# ProbeStationRelayBoard.net
KiCad netlist of a schematic drawn in EAGLE
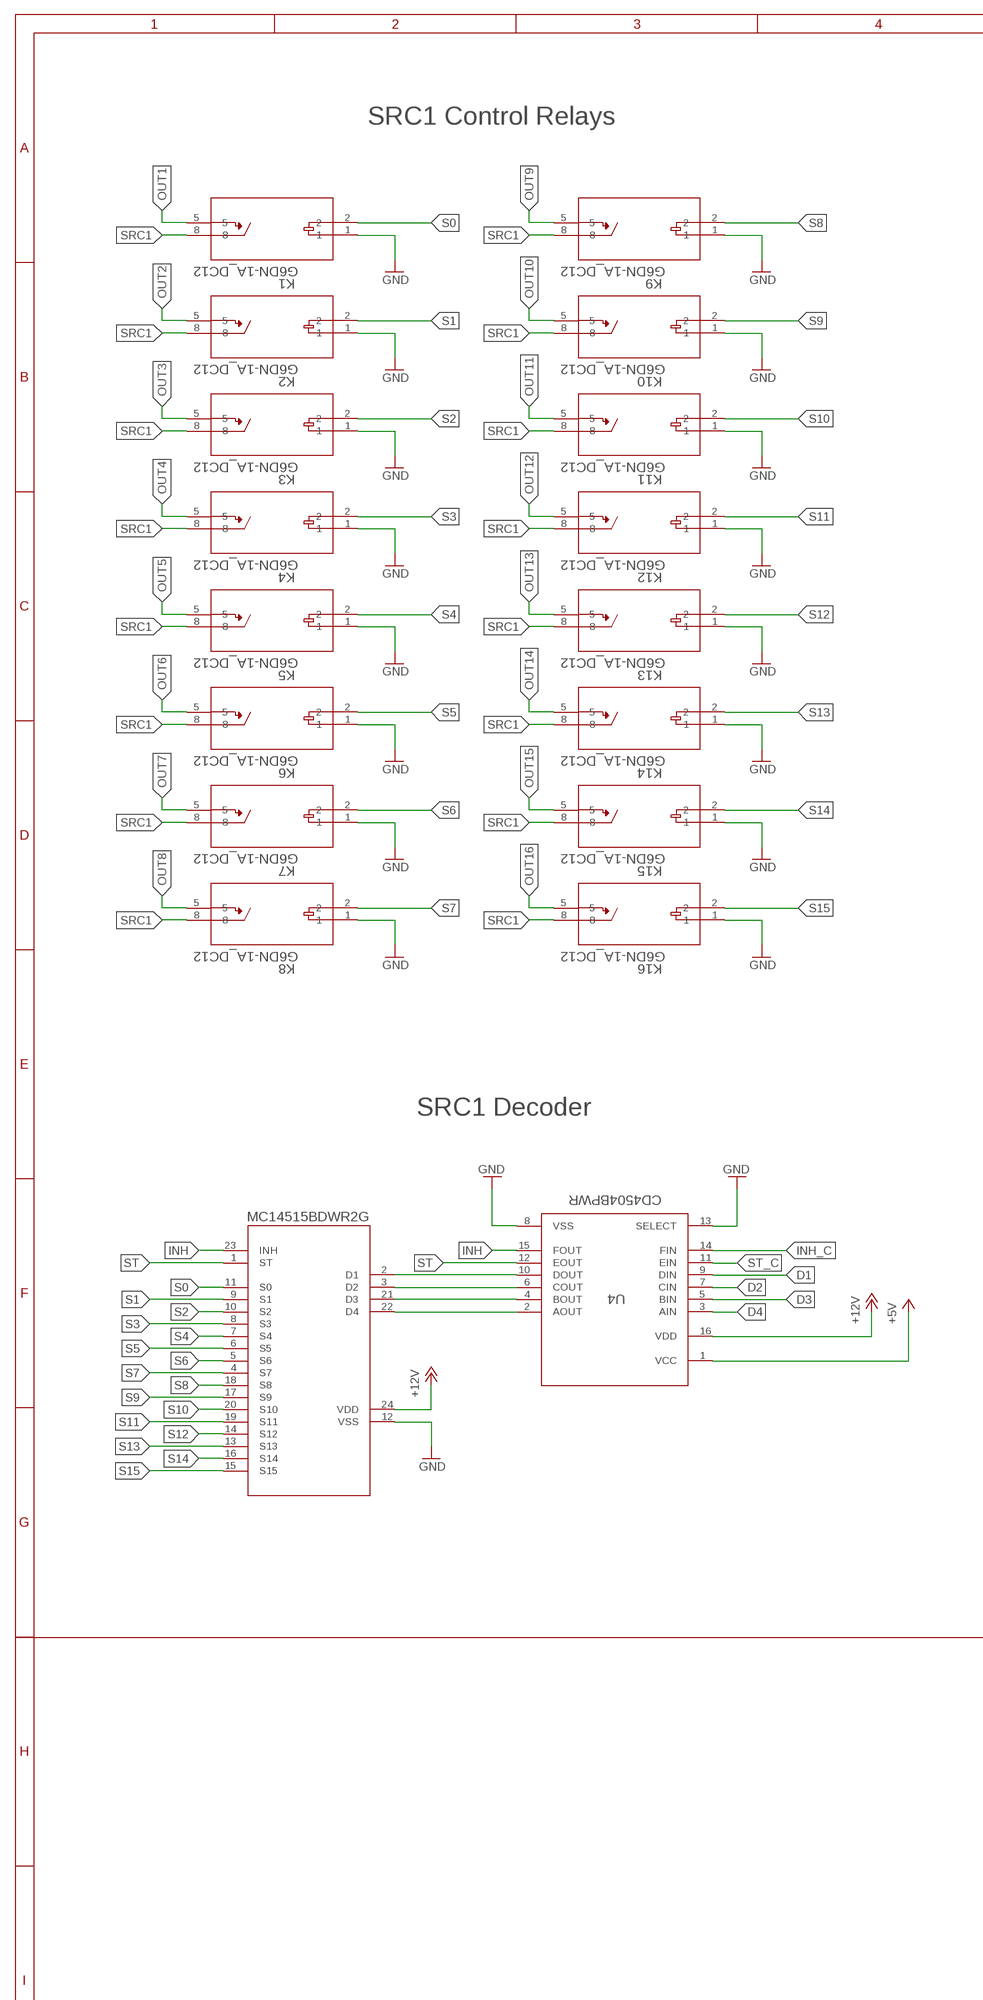
[diagram p0: schematic, sheet 1, part 1 of 2]
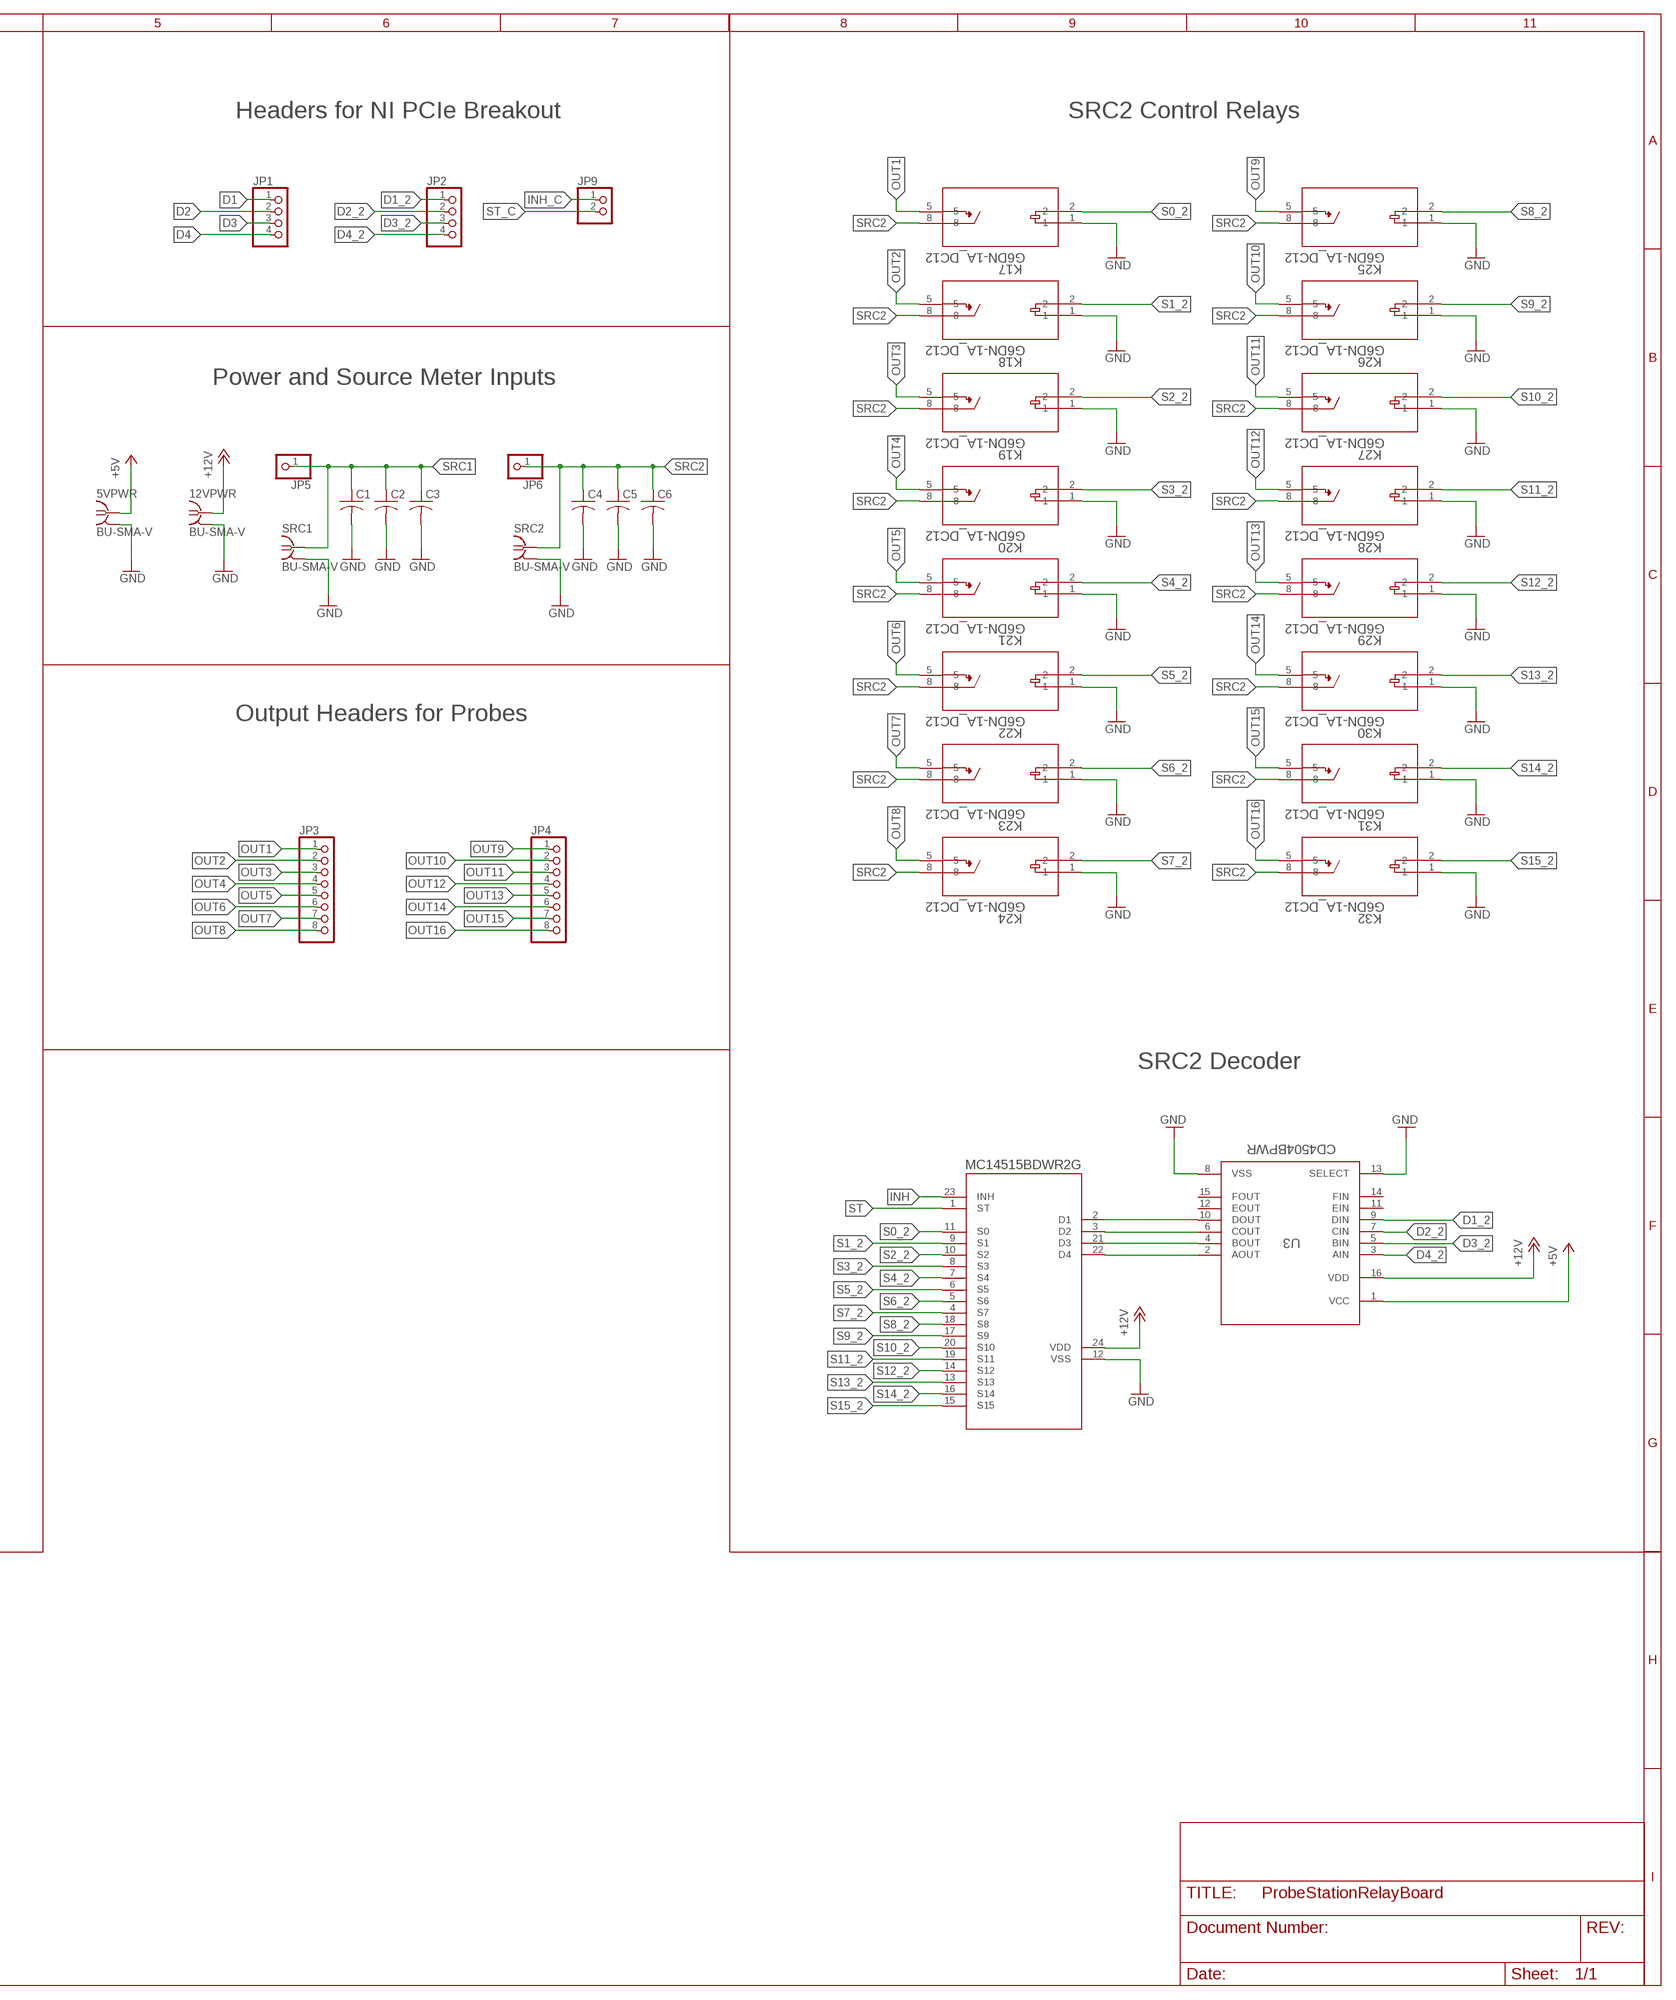
[diagram p1: schematic, sheet 1, part 2 of 2]

(export (version "E")
  (design (tool "Eeschema 10.0.6"))
  (components
    (comp (ref "5VPWR")
      (value "BU-SMA-V")
      (footprint "eagle-import:BU-SMA-V")
      (libsource (lib "eagle-import") (part "BU-SMA-V"))
    )
    (comp (ref "12VPWR")
      (value "BU-SMA-V")
      (footprint "eagle-import:BU-SMA-V")
      (libsource (lib "eagle-import") (part "BU-SMA-V"))
    )
    (comp (ref "C1")
      (value "C-USC0805")
      (footprint "eagle-import:C0805")
      (libsource (lib "eagle-import") (part "C-USC0805"))
    )
    (comp (ref "C2")
      (value "C-USC0805")
      (footprint "eagle-import:C0805")
      (libsource (lib "eagle-import") (part "C-USC0805"))
    )
    (comp (ref "C3")
      (value "C-USC0805")
      (footprint "eagle-import:C0805")
      (libsource (lib "eagle-import") (part "C-USC0805"))
    )
    (comp (ref "C4")
      (value "C-USC0805")
      (footprint "eagle-import:C0805")
      (libsource (lib "eagle-import") (part "C-USC0805"))
    )
    (comp (ref "C5")
      (value "C-USC0805")
      (footprint "eagle-import:C0805")
      (libsource (lib "eagle-import") (part "C-USC0805"))
    )
    (comp (ref "C6")
      (value "C-USC0805")
      (footprint "eagle-import:C0805")
      (libsource (lib "eagle-import") (part "C-USC0805"))
    )
    (comp (ref "JP1")
      (value "PINHD-1X4")
      (footprint "eagle-import:1X04")
      (libsource (lib "eagle-import") (part "PINHD-1X4"))
    )
    (comp (ref "JP2")
      (value "PINHD-1X4")
      (footprint "eagle-import:1X04")
      (libsource (lib "eagle-import") (part "PINHD-1X4"))
    )
    (comp (ref "JP3")
      (value "PINHD-1X8")
      (footprint "eagle-import:1X08")
      (libsource (lib "eagle-import") (part "PINHD-1X8"))
    )
    (comp (ref "JP4")
      (value "PINHD-1X8")
      (footprint "eagle-import:1X08")
      (libsource (lib "eagle-import") (part "PINHD-1X8"))
    )
    (comp (ref "JP5")
      (value "PINHD-1X1")
      (footprint "eagle-import:1X01")
      (libsource (lib "eagle-import") (part "PINHD-1X1"))
    )
    (comp (ref "JP6")
      (value "PINHD-1X1")
      (footprint "eagle-import:1X01")
      (libsource (lib "eagle-import") (part "PINHD-1X1"))
    )
    (comp (ref "JP9")
      (value "PINHD-1X2")
      (footprint "eagle-import:1X02")
      (libsource (lib "eagle-import") (part "PINHD-1X2"))
    )
    (comp (ref "K1")
      (value "G6DN-1A_DC12")
      (footprint "eagle-import:RELAY_G6DN-1A_OMR")
      (fields
        (field (name "MANUFACTURER_PART_NUMBER") "G6DN-1A DC12")
        (field (name "COPYRIGHT") "Copyright (C) 2021 Ultra Librarian. All rights reserved.")
      )
      (libsource (lib "eagle-import") (part "G6DN-1A_DC12"))
    )
    (comp (ref "K2")
      (value "G6DN-1A_DC12")
      (footprint "eagle-import:RELAY_G6DN-1A_OMR")
      (fields
        (field (name "MANUFACTURER_PART_NUMBER") "G6DN-1A DC12")
        (field (name "COPYRIGHT") "Copyright (C) 2021 Ultra Librarian. All rights reserved.")
      )
      (libsource (lib "eagle-import") (part "G6DN-1A_DC12"))
    )
    (comp (ref "K3")
      (value "G6DN-1A_DC12")
      (footprint "eagle-import:RELAY_G6DN-1A_OMR")
      (fields
        (field (name "MANUFACTURER_PART_NUMBER") "G6DN-1A DC12")
        (field (name "COPYRIGHT") "Copyright (C) 2021 Ultra Librarian. All rights reserved.")
      )
      (libsource (lib "eagle-import") (part "G6DN-1A_DC12"))
    )
    (comp (ref "K4")
      (value "G6DN-1A_DC12")
      (footprint "eagle-import:RELAY_G6DN-1A_OMR")
      (fields
        (field (name "MANUFACTURER_PART_NUMBER") "G6DN-1A DC12")
        (field (name "COPYRIGHT") "Copyright (C) 2021 Ultra Librarian. All rights reserved.")
      )
      (libsource (lib "eagle-import") (part "G6DN-1A_DC12"))
    )
    (comp (ref "K5")
      (value "G6DN-1A_DC12")
      (footprint "eagle-import:RELAY_G6DN-1A_OMR")
      (fields
        (field (name "MANUFACTURER_PART_NUMBER") "G6DN-1A DC12")
        (field (name "COPYRIGHT") "Copyright (C) 2021 Ultra Librarian. All rights reserved.")
      )
      (libsource (lib "eagle-import") (part "G6DN-1A_DC12"))
    )
    (comp (ref "K6")
      (value "G6DN-1A_DC12")
      (footprint "eagle-import:RELAY_G6DN-1A_OMR")
      (fields
        (field (name "MANUFACTURER_PART_NUMBER") "G6DN-1A DC12")
        (field (name "COPYRIGHT") "Copyright (C) 2021 Ultra Librarian. All rights reserved.")
      )
      (libsource (lib "eagle-import") (part "G6DN-1A_DC12"))
    )
    (comp (ref "K7")
      (value "G6DN-1A_DC12")
      (footprint "eagle-import:RELAY_G6DN-1A_OMR")
      (fields
        (field (name "MANUFACTURER_PART_NUMBER") "G6DN-1A DC12")
        (field (name "COPYRIGHT") "Copyright (C) 2021 Ultra Librarian. All rights reserved.")
      )
      (libsource (lib "eagle-import") (part "G6DN-1A_DC12"))
    )
    (comp (ref "K8")
      (value "G6DN-1A_DC12")
      (footprint "eagle-import:RELAY_G6DN-1A_OMR")
      (fields
        (field (name "MANUFACTURER_PART_NUMBER") "G6DN-1A DC12")
        (field (name "COPYRIGHT") "Copyright (C) 2021 Ultra Librarian. All rights reserved.")
      )
      (libsource (lib "eagle-import") (part "G6DN-1A_DC12"))
    )
    (comp (ref "K9")
      (value "G6DN-1A_DC12")
      (footprint "eagle-import:RELAY_G6DN-1A_OMR")
      (fields
        (field (name "MANUFACTURER_PART_NUMBER") "G6DN-1A DC12")
        (field (name "COPYRIGHT") "Copyright (C) 2021 Ultra Librarian. All rights reserved.")
      )
      (libsource (lib "eagle-import") (part "G6DN-1A_DC12"))
    )
    (comp (ref "K10")
      (value "G6DN-1A_DC12")
      (footprint "eagle-import:RELAY_G6DN-1A_OMR")
      (fields
        (field (name "MANUFACTURER_PART_NUMBER") "G6DN-1A DC12")
        (field (name "COPYRIGHT") "Copyright (C) 2021 Ultra Librarian. All rights reserved.")
      )
      (libsource (lib "eagle-import") (part "G6DN-1A_DC12"))
    )
    (comp (ref "K11")
      (value "G6DN-1A_DC12")
      (footprint "eagle-import:RELAY_G6DN-1A_OMR")
      (fields
        (field (name "MANUFACTURER_PART_NUMBER") "G6DN-1A DC12")
        (field (name "COPYRIGHT") "Copyright (C) 2021 Ultra Librarian. All rights reserved.")
      )
      (libsource (lib "eagle-import") (part "G6DN-1A_DC12"))
    )
    (comp (ref "K12")
      (value "G6DN-1A_DC12")
      (footprint "eagle-import:RELAY_G6DN-1A_OMR")
      (fields
        (field (name "MANUFACTURER_PART_NUMBER") "G6DN-1A DC12")
        (field (name "COPYRIGHT") "Copyright (C) 2021 Ultra Librarian. All rights reserved.")
      )
      (libsource (lib "eagle-import") (part "G6DN-1A_DC12"))
    )
    (comp (ref "K13")
      (value "G6DN-1A_DC12")
      (footprint "eagle-import:RELAY_G6DN-1A_OMR")
      (fields
        (field (name "MANUFACTURER_PART_NUMBER") "G6DN-1A DC12")
        (field (name "COPYRIGHT") "Copyright (C) 2021 Ultra Librarian. All rights reserved.")
      )
      (libsource (lib "eagle-import") (part "G6DN-1A_DC12"))
    )
    (comp (ref "K14")
      (value "G6DN-1A_DC12")
      (footprint "eagle-import:RELAY_G6DN-1A_OMR")
      (fields
        (field (name "MANUFACTURER_PART_NUMBER") "G6DN-1A DC12")
        (field (name "COPYRIGHT") "Copyright (C) 2021 Ultra Librarian. All rights reserved.")
      )
      (libsource (lib "eagle-import") (part "G6DN-1A_DC12"))
    )
    (comp (ref "K15")
      (value "G6DN-1A_DC12")
      (footprint "eagle-import:RELAY_G6DN-1A_OMR")
      (fields
        (field (name "MANUFACTURER_PART_NUMBER") "G6DN-1A DC12")
        (field (name "COPYRIGHT") "Copyright (C) 2021 Ultra Librarian. All rights reserved.")
      )
      (libsource (lib "eagle-import") (part "G6DN-1A_DC12"))
    )
    (comp (ref "K16")
      (value "G6DN-1A_DC12")
      (footprint "eagle-import:RELAY_G6DN-1A_OMR")
      (fields
        (field (name "MANUFACTURER_PART_NUMBER") "G6DN-1A DC12")
        (field (name "COPYRIGHT") "Copyright (C) 2021 Ultra Librarian. All rights reserved.")
      )
      (libsource (lib "eagle-import") (part "G6DN-1A_DC12"))
    )
    (comp (ref "K17")
      (value "G6DN-1A_DC12")
      (footprint "eagle-import:RELAY_G6DN-1A_OMR")
      (fields
        (field (name "MANUFACTURER_PART_NUMBER") "G6DN-1A DC12")
        (field (name "COPYRIGHT") "Copyright (C) 2021 Ultra Librarian. All rights reserved.")
      )
      (libsource (lib "eagle-import") (part "G6DN-1A_DC12"))
    )
    (comp (ref "K18")
      (value "G6DN-1A_DC12")
      (footprint "eagle-import:RELAY_G6DN-1A_OMR")
      (fields
        (field (name "MANUFACTURER_PART_NUMBER") "G6DN-1A DC12")
        (field (name "COPYRIGHT") "Copyright (C) 2021 Ultra Librarian. All rights reserved.")
      )
      (libsource (lib "eagle-import") (part "G6DN-1A_DC12"))
    )
    (comp (ref "K19")
      (value "G6DN-1A_DC12")
      (footprint "eagle-import:RELAY_G6DN-1A_OMR")
      (fields
        (field (name "MANUFACTURER_PART_NUMBER") "G6DN-1A DC12")
        (field (name "COPYRIGHT") "Copyright (C) 2021 Ultra Librarian. All rights reserved.")
      )
      (libsource (lib "eagle-import") (part "G6DN-1A_DC12"))
    )
    (comp (ref "K20")
      (value "G6DN-1A_DC12")
      (footprint "eagle-import:RELAY_G6DN-1A_OMR")
      (fields
        (field (name "MANUFACTURER_PART_NUMBER") "G6DN-1A DC12")
        (field (name "COPYRIGHT") "Copyright (C) 2021 Ultra Librarian. All rights reserved.")
      )
      (libsource (lib "eagle-import") (part "G6DN-1A_DC12"))
    )
    (comp (ref "K21")
      (value "G6DN-1A_DC12")
      (footprint "eagle-import:RELAY_G6DN-1A_OMR")
      (fields
        (field (name "MANUFACTURER_PART_NUMBER") "G6DN-1A DC12")
        (field (name "COPYRIGHT") "Copyright (C) 2021 Ultra Librarian. All rights reserved.")
      )
      (libsource (lib "eagle-import") (part "G6DN-1A_DC12"))
    )
    (comp (ref "K22")
      (value "G6DN-1A_DC12")
      (footprint "eagle-import:RELAY_G6DN-1A_OMR")
      (fields
        (field (name "MANUFACTURER_PART_NUMBER") "G6DN-1A DC12")
        (field (name "COPYRIGHT") "Copyright (C) 2021 Ultra Librarian. All rights reserved.")
      )
      (libsource (lib "eagle-import") (part "G6DN-1A_DC12"))
    )
    (comp (ref "K23")
      (value "G6DN-1A_DC12")
      (footprint "eagle-import:RELAY_G6DN-1A_OMR")
      (fields
        (field (name "MANUFACTURER_PART_NUMBER") "G6DN-1A DC12")
        (field (name "COPYRIGHT") "Copyright (C) 2021 Ultra Librarian. All rights reserved.")
      )
      (libsource (lib "eagle-import") (part "G6DN-1A_DC12"))
    )
    (comp (ref "K24")
      (value "G6DN-1A_DC12")
      (footprint "eagle-import:RELAY_G6DN-1A_OMR")
      (fields
        (field (name "MANUFACTURER_PART_NUMBER") "G6DN-1A DC12")
        (field (name "COPYRIGHT") "Copyright (C) 2021 Ultra Librarian. All rights reserved.")
      )
      (libsource (lib "eagle-import") (part "G6DN-1A_DC12"))
    )
    (comp (ref "K25")
      (value "G6DN-1A_DC12")
      (footprint "eagle-import:RELAY_G6DN-1A_OMR")
      (fields
        (field (name "MANUFACTURER_PART_NUMBER") "G6DN-1A DC12")
        (field (name "COPYRIGHT") "Copyright (C) 2021 Ultra Librarian. All rights reserved.")
      )
      (libsource (lib "eagle-import") (part "G6DN-1A_DC12"))
    )
    (comp (ref "K26")
      (value "G6DN-1A_DC12")
      (footprint "eagle-import:RELAY_G6DN-1A_OMR")
      (fields
        (field (name "MANUFACTURER_PART_NUMBER") "G6DN-1A DC12")
        (field (name "COPYRIGHT") "Copyright (C) 2021 Ultra Librarian. All rights reserved.")
      )
      (libsource (lib "eagle-import") (part "G6DN-1A_DC12"))
    )
    (comp (ref "K27")
      (value "G6DN-1A_DC12")
      (footprint "eagle-import:RELAY_G6DN-1A_OMR")
      (fields
        (field (name "MANUFACTURER_PART_NUMBER") "G6DN-1A DC12")
        (field (name "COPYRIGHT") "Copyright (C) 2021 Ultra Librarian. All rights reserved.")
      )
      (libsource (lib "eagle-import") (part "G6DN-1A_DC12"))
    )
    (comp (ref "K28")
      (value "G6DN-1A_DC12")
      (footprint "eagle-import:RELAY_G6DN-1A_OMR")
      (fields
        (field (name "MANUFACTURER_PART_NUMBER") "G6DN-1A DC12")
        (field (name "COPYRIGHT") "Copyright (C) 2021 Ultra Librarian. All rights reserved.")
      )
      (libsource (lib "eagle-import") (part "G6DN-1A_DC12"))
    )
    (comp (ref "K29")
      (value "G6DN-1A_DC12")
      (footprint "eagle-import:RELAY_G6DN-1A_OMR")
      (fields
        (field (name "MANUFACTURER_PART_NUMBER") "G6DN-1A DC12")
        (field (name "COPYRIGHT") "Copyright (C) 2021 Ultra Librarian. All rights reserved.")
      )
      (libsource (lib "eagle-import") (part "G6DN-1A_DC12"))
    )
    (comp (ref "K30")
      (value "G6DN-1A_DC12")
      (footprint "eagle-import:RELAY_G6DN-1A_OMR")
      (fields
        (field (name "MANUFACTURER_PART_NUMBER") "G6DN-1A DC12")
        (field (name "COPYRIGHT") "Copyright (C) 2021 Ultra Librarian. All rights reserved.")
      )
      (libsource (lib "eagle-import") (part "G6DN-1A_DC12"))
    )
    (comp (ref "K31")
      (value "G6DN-1A_DC12")
      (footprint "eagle-import:RELAY_G6DN-1A_OMR")
      (fields
        (field (name "MANUFACTURER_PART_NUMBER") "G6DN-1A DC12")
        (field (name "COPYRIGHT") "Copyright (C) 2021 Ultra Librarian. All rights reserved.")
      )
      (libsource (lib "eagle-import") (part "G6DN-1A_DC12"))
    )
    (comp (ref "K32")
      (value "G6DN-1A_DC12")
      (footprint "eagle-import:RELAY_G6DN-1A_OMR")
      (fields
        (field (name "MANUFACTURER_PART_NUMBER") "G6DN-1A DC12")
        (field (name "COPYRIGHT") "Copyright (C) 2021 Ultra Librarian. All rights reserved.")
      )
      (libsource (lib "eagle-import") (part "G6DN-1A_DC12"))
    )
    (comp (ref "SRC1")
      (value "BU-SMA-V")
      (footprint "eagle-import:BU-SMA-V")
      (libsource (lib "eagle-import") (part "BU-SMA-V"))
    )
    (comp (ref "SRC2")
      (value "BU-SMA-V")
      (footprint "eagle-import:BU-SMA-V")
      (libsource (lib "eagle-import") (part "BU-SMA-V"))
    )
    (comp (ref "U1")
      (value "MC14515BDWR2G")
      (footprint "eagle-import:SOIC-24WB_ONS")
      (fields (field (name "COPYRIGHT") "Copyright (C) 2021 Ultra Librarian. All rights reserved."))
      (libsource (lib "eagle-import") (part "MC14515BDWR2G"))
    )
    (comp (ref "U2")
      (value "MC14515BDWR2G")
      (footprint "eagle-import:SOIC-24WB_ONS")
      (fields (field (name "COPYRIGHT") "Copyright (C) 2021 Ultra Librarian. All rights reserved."))
      (libsource (lib "eagle-import") (part "MC14515BDWR2G"))
    )
    (comp (ref "U3")
      (value "CD4504BPWR")
      (footprint "eagle-import:PW0016A_N")
      (fields (field (name "COPYRIGHT") "Copyright (C) 2021 Ultra Librarian. All rights reserved."))
      (libsource (lib "eagle-import") (part "CD4504BPWR"))
    )
    (comp (ref "U4")
      (value "CD4504BPWR")
      (footprint "eagle-import:PW0016A_N")
      (fields (field (name "COPYRIGHT") "Copyright (C) 2021 Ultra Librarian. All rights reserved."))
      (libsource (lib "eagle-import") (part "CD4504BPWR"))
    )
  )
  (nets
    (net (code "1") (name "+5V") (class "Default")
      (node (ref "5VPWR") (pin "1") (pinfunction "1_1") (pintype "passive"))
      (node (ref "U3") (pin "1") (pinfunction "VCC_1") (pintype "power_in"))
      (node (ref "U4") (pin "1") (pinfunction "VCC_1") (pintype "power_in"))
    )
    (net (code "2") (name "+12V") (class "Default")
      (node (ref "12VPWR") (pin "1") (pinfunction "1_1") (pintype "passive"))
      (node (ref "U1") (pin "24") (pinfunction "VDD_24") (pintype "power_in"))
      (node (ref "U2") (pin "24") (pinfunction "VDD_24") (pintype "power_in"))
      (node (ref "U3") (pin "16") (pinfunction "VDD_16") (pintype "power_in"))
      (node (ref "U4") (pin "16") (pinfunction "VDD_16") (pintype "power_in"))
    )
    (net (code "3") (name "D1") (class "Default")
      (node (ref "JP1") (pin "1") (pinfunction "1_1") (pintype "passive"))
      (node (ref "U4") (pin "9") (pinfunction "DIN_9") (pintype "input"))
    )
    (net (code "4") (name "D1_2") (class "Default")
      (node (ref "JP2") (pin "1") (pinfunction "1_1") (pintype "passive"))
      (node (ref "U3") (pin "9") (pinfunction "DIN_9") (pintype "input"))
    )
    (net (code "5") (name "D2") (class "Default")
      (node (ref "JP1") (pin "2") (pinfunction "2_2") (pintype "passive"))
      (node (ref "U4") (pin "7") (pinfunction "CIN_7") (pintype "input"))
    )
    (net (code "6") (name "D2_2") (class "Default")
      (node (ref "JP2") (pin "2") (pinfunction "2_2") (pintype "passive"))
      (node (ref "U3") (pin "7") (pinfunction "CIN_7") (pintype "input"))
    )
    (net (code "7") (name "D3") (class "Default")
      (node (ref "JP1") (pin "3") (pinfunction "3_3") (pintype "passive"))
      (node (ref "U4") (pin "5") (pinfunction "BIN_5") (pintype "input"))
    )
    (net (code "8") (name "D3_2") (class "Default")
      (node (ref "JP2") (pin "3") (pinfunction "3_3") (pintype "passive"))
      (node (ref "U3") (pin "5") (pinfunction "BIN_5") (pintype "input"))
    )
    (net (code "9") (name "D4") (class "Default")
      (node (ref "JP1") (pin "4") (pinfunction "4_4") (pintype "passive"))
      (node (ref "U4") (pin "3") (pinfunction "AIN_3") (pintype "input"))
    )
    (net (code "10") (name "D4_2") (class "Default")
      (node (ref "JP2") (pin "4") (pinfunction "4_4") (pintype "passive"))
      (node (ref "U3") (pin "3") (pinfunction "AIN_3") (pintype "input"))
    )
    (net (code "11") (name "GND") (class "Default")
      (node (ref "12VPWR") (pin "2") (pinfunction "2_2") (pintype "passive"))
      (node (ref "12VPWR") (pin "3") (pinfunction "2_3") (pintype "passive"))
      (node (ref "12VPWR") (pin "4") (pinfunction "2_4") (pintype "passive"))
      (node (ref "12VPWR") (pin "5") (pinfunction "2_5") (pintype "passive"))
      (node (ref "5VPWR") (pin "2") (pinfunction "2_2") (pintype "passive"))
      (node (ref "5VPWR") (pin "3") (pinfunction "2_3") (pintype "passive"))
      (node (ref "5VPWR") (pin "4") (pinfunction "2_4") (pintype "passive"))
      (node (ref "5VPWR") (pin "5") (pinfunction "2_5") (pintype "passive"))
      (node (ref "C1") (pin "2") (pinfunction "2_2") (pintype "passive"))
      (node (ref "C2") (pin "2") (pinfunction "2_2") (pintype "passive"))
      (node (ref "C3") (pin "2") (pinfunction "2_2") (pintype "passive"))
      (node (ref "C4") (pin "2") (pinfunction "2_2") (pintype "passive"))
      (node (ref "C5") (pin "2") (pinfunction "2_2") (pintype "passive"))
      (node (ref "C6") (pin "2") (pinfunction "2_2") (pintype "passive"))
      (node (ref "K1") (pin "1") (pinfunction "1_1") (pintype "passive"))
      (node (ref "K10") (pin "1") (pinfunction "1_1") (pintype "passive"))
      (node (ref "K11") (pin "1") (pinfunction "1_1") (pintype "passive"))
      (node (ref "K12") (pin "1") (pinfunction "1_1") (pintype "passive"))
      (node (ref "K13") (pin "1") (pinfunction "1_1") (pintype "passive"))
      (node (ref "K14") (pin "1") (pinfunction "1_1") (pintype "passive"))
      (node (ref "K15") (pin "1") (pinfunction "1_1") (pintype "passive"))
      (node (ref "K16") (pin "1") (pinfunction "1_1") (pintype "passive"))
      (node (ref "K17") (pin "1") (pinfunction "1_1") (pintype "passive"))
      (node (ref "K18") (pin "1") (pinfunction "1_1") (pintype "passive"))
      (node (ref "K19") (pin "1") (pinfunction "1_1") (pintype "passive"))
      (node (ref "K2") (pin "1") (pinfunction "1_1") (pintype "passive"))
      (node (ref "K20") (pin "1") (pinfunction "1_1") (pintype "passive"))
      (node (ref "K21") (pin "1") (pinfunction "1_1") (pintype "passive"))
      (node (ref "K22") (pin "1") (pinfunction "1_1") (pintype "passive"))
      (node (ref "K23") (pin "1") (pinfunction "1_1") (pintype "passive"))
      (node (ref "K24") (pin "1") (pinfunction "1_1") (pintype "passive"))
      (node (ref "K25") (pin "1") (pinfunction "1_1") (pintype "passive"))
      (node (ref "K26") (pin "1") (pinfunction "1_1") (pintype "passive"))
      (node (ref "K27") (pin "1") (pinfunction "1_1") (pintype "passive"))
      (node (ref "K28") (pin "1") (pinfunction "1_1") (pintype "passive"))
      (node (ref "K29") (pin "1") (pinfunction "1_1") (pintype "passive"))
      (node (ref "K3") (pin "1") (pinfunction "1_1") (pintype "passive"))
      (node (ref "K30") (pin "1") (pinfunction "1_1") (pintype "passive"))
      (node (ref "K31") (pin "1") (pinfunction "1_1") (pintype "passive"))
      (node (ref "K32") (pin "1") (pinfunction "1_1") (pintype "passive"))
      (node (ref "K4") (pin "1") (pinfunction "1_1") (pintype "passive"))
      (node (ref "K5") (pin "1") (pinfunction "1_1") (pintype "passive"))
      (node (ref "K6") (pin "1") (pinfunction "1_1") (pintype "passive"))
      (node (ref "K7") (pin "1") (pinfunction "1_1") (pintype "passive"))
      (node (ref "K8") (pin "1") (pinfunction "1_1") (pintype "passive"))
      (node (ref "K9") (pin "1") (pinfunction "1_1") (pintype "passive"))
      (node (ref "SRC1") (pin "2") (pinfunction "2_2") (pintype "passive"))
      (node (ref "SRC1") (pin "3") (pinfunction "2_3") (pintype "passive"))
      (node (ref "SRC1") (pin "4") (pinfunction "2_4") (pintype "passive"))
      (node (ref "SRC1") (pin "5") (pinfunction "2_5") (pintype "passive"))
      (node (ref "SRC2") (pin "2") (pinfunction "2_2") (pintype "passive"))
      (node (ref "SRC2") (pin "3") (pinfunction "2_3") (pintype "passive"))
      (node (ref "SRC2") (pin "4") (pinfunction "2_4") (pintype "passive"))
      (node (ref "SRC2") (pin "5") (pinfunction "2_5") (pintype "passive"))
      (node (ref "U1") (pin "12") (pinfunction "VSS_12") (pintype "power_in"))
      (node (ref "U2") (pin "12") (pinfunction "VSS_12") (pintype "power_in"))
      (node (ref "U3") (pin "13") (pinfunction "SELECT_13") (pintype "input"))
      (node (ref "U3") (pin "8") (pinfunction "VSS_8") (pintype "power_in"))
      (node (ref "U4") (pin "13") (pinfunction "SELECT_13") (pintype "input"))
      (node (ref "U4") (pin "8") (pinfunction "VSS_8") (pintype "power_in"))
    )
    (net (code "12") (name "INH") (class "Default")
      (node (ref "U1") (pin "23") (pinfunction "INH_23") (pintype "passive"))
      (node (ref "U2") (pin "23") (pinfunction "INH_23") (pintype "passive"))
      (node (ref "U4") (pin "15") (pinfunction "FOUT_15") (pintype "output"))
    )
    (net (code "13") (name "INH_C") (class "Default")
      (node (ref "JP9") (pin "1") (pinfunction "1_1") (pintype "passive"))
      (node (ref "U4") (pin "14") (pinfunction "FIN_14") (pintype "input"))
    )
    (net (code "14") (name "Net-(U1-D1)") (class "Default")
      (node (ref "U1") (pin "2") (pinfunction "D1_2") (pintype "passive"))
      (node (ref "U3") (pin "10") (pinfunction "DOUT_10") (pintype "output"))
    )
    (net (code "15") (name "Net-(U1-D2)") (class "Default")
      (node (ref "U1") (pin "3") (pinfunction "D2_3") (pintype "passive"))
      (node (ref "U3") (pin "6") (pinfunction "COUT_6") (pintype "output"))
    )
    (net (code "16") (name "Net-(U1-D3)") (class "Default")
      (node (ref "U1") (pin "21") (pinfunction "D3_21") (pintype "passive"))
      (node (ref "U3") (pin "4") (pinfunction "BOUT_4") (pintype "output"))
    )
    (net (code "17") (name "Net-(U1-D4)") (class "Default")
      (node (ref "U1") (pin "22") (pinfunction "D4_22") (pintype "passive"))
      (node (ref "U3") (pin "2") (pinfunction "AOUT_2") (pintype "output"))
    )
    (net (code "18") (name "Net-(U2-D1)") (class "Default")
      (node (ref "U2") (pin "2") (pinfunction "D1_2") (pintype "passive"))
      (node (ref "U4") (pin "10") (pinfunction "DOUT_10") (pintype "output"))
    )
    (net (code "19") (name "Net-(U2-D2)") (class "Default")
      (node (ref "U2") (pin "3") (pinfunction "D2_3") (pintype "passive"))
      (node (ref "U4") (pin "6") (pinfunction "COUT_6") (pintype "output"))
    )
    (net (code "20") (name "Net-(U2-D3)") (class "Default")
      (node (ref "U2") (pin "21") (pinfunction "D3_21") (pintype "passive"))
      (node (ref "U4") (pin "4") (pinfunction "BOUT_4") (pintype "output"))
    )
    (net (code "21") (name "Net-(U2-D4)") (class "Default")
      (node (ref "U2") (pin "22") (pinfunction "D4_22") (pintype "passive"))
      (node (ref "U4") (pin "2") (pinfunction "AOUT_2") (pintype "output"))
    )
    (net (code "22") (name "OUT1") (class "Default")
      (node (ref "JP3") (pin "1") (pinfunction "1_1") (pintype "passive"))
      (node (ref "K1") (pin "5") (pinfunction "5_5") (pintype "passive"))
      (node (ref "K17") (pin "5") (pinfunction "5_5") (pintype "passive"))
    )
    (net (code "23") (name "OUT2") (class "Default")
      (node (ref "JP3") (pin "2") (pinfunction "2_2") (pintype "passive"))
      (node (ref "K18") (pin "5") (pinfunction "5_5") (pintype "passive"))
      (node (ref "K2") (pin "5") (pinfunction "5_5") (pintype "passive"))
    )
    (net (code "24") (name "OUT3") (class "Default")
      (node (ref "JP3") (pin "3") (pinfunction "3_3") (pintype "passive"))
      (node (ref "K19") (pin "5") (pinfunction "5_5") (pintype "passive"))
      (node (ref "K3") (pin "5") (pinfunction "5_5") (pintype "passive"))
    )
    (net (code "25") (name "OUT4") (class "Default")
      (node (ref "JP3") (pin "4") (pinfunction "4_4") (pintype "passive"))
      (node (ref "K20") (pin "5") (pinfunction "5_5") (pintype "passive"))
      (node (ref "K4") (pin "5") (pinfunction "5_5") (pintype "passive"))
    )
    (net (code "26") (name "OUT5") (class "Default")
      (node (ref "JP3") (pin "5") (pinfunction "5_5") (pintype "passive"))
      (node (ref "K21") (pin "5") (pinfunction "5_5") (pintype "passive"))
      (node (ref "K5") (pin "5") (pinfunction "5_5") (pintype "passive"))
    )
    (net (code "27") (name "OUT6") (class "Default")
      (node (ref "JP3") (pin "6") (pinfunction "6_6") (pintype "passive"))
      (node (ref "K22") (pin "5") (pinfunction "5_5") (pintype "passive"))
      (node (ref "K6") (pin "5") (pinfunction "5_5") (pintype "passive"))
    )
    (net (code "28") (name "OUT7") (class "Default")
      (node (ref "JP3") (pin "7") (pinfunction "7_7") (pintype "passive"))
      (node (ref "K23") (pin "5") (pinfunction "5_5") (pintype "passive"))
      (node (ref "K7") (pin "5") (pinfunction "5_5") (pintype "passive"))
    )
    (net (code "29") (name "OUT8") (class "Default")
      (node (ref "JP3") (pin "8") (pinfunction "8_8") (pintype "passive"))
      (node (ref "K24") (pin "5") (pinfunction "5_5") (pintype "passive"))
      (node (ref "K8") (pin "5") (pinfunction "5_5") (pintype "passive"))
    )
    (net (code "30") (name "OUT9") (class "Default")
      (node (ref "JP4") (pin "1") (pinfunction "1_1") (pintype "passive"))
      (node (ref "K25") (pin "5") (pinfunction "5_5") (pintype "passive"))
      (node (ref "K9") (pin "5") (pinfunction "5_5") (pintype "passive"))
    )
    (net (code "31") (name "OUT10") (class "Default")
      (node (ref "JP4") (pin "2") (pinfunction "2_2") (pintype "passive"))
      (node (ref "K10") (pin "5") (pinfunction "5_5") (pintype "passive"))
      (node (ref "K26") (pin "5") (pinfunction "5_5") (pintype "passive"))
    )
    (net (code "32") (name "OUT11") (class "Default")
      (node (ref "JP4") (pin "3") (pinfunction "3_3") (pintype "passive"))
      (node (ref "K11") (pin "5") (pinfunction "5_5") (pintype "passive"))
      (node (ref "K27") (pin "5") (pinfunction "5_5") (pintype "passive"))
    )
    (net (code "33") (name "OUT12") (class "Default")
      (node (ref "JP4") (pin "4") (pinfunction "4_4") (pintype "passive"))
      (node (ref "K12") (pin "5") (pinfunction "5_5") (pintype "passive"))
      (node (ref "K28") (pin "5") (pinfunction "5_5") (pintype "passive"))
    )
    (net (code "34") (name "OUT13") (class "Default")
      (node (ref "JP4") (pin "5") (pinfunction "5_5") (pintype "passive"))
      (node (ref "K13") (pin "5") (pinfunction "5_5") (pintype "passive"))
      (node (ref "K29") (pin "5") (pinfunction "5_5") (pintype "passive"))
    )
    (net (code "35") (name "OUT14") (class "Default")
      (node (ref "JP4") (pin "6") (pinfunction "6_6") (pintype "passive"))
      (node (ref "K14") (pin "5") (pinfunction "5_5") (pintype "passive"))
      (node (ref "K30") (pin "5") (pinfunction "5_5") (pintype "passive"))
    )
    (net (code "36") (name "OUT15") (class "Default")
      (node (ref "JP4") (pin "7") (pinfunction "7_7") (pintype "passive"))
      (node (ref "K15") (pin "5") (pinfunction "5_5") (pintype "passive"))
      (node (ref "K31") (pin "5") (pinfunction "5_5") (pintype "passive"))
    )
    (net (code "37") (name "OUT16") (class "Default")
      (node (ref "JP4") (pin "8") (pinfunction "8_8") (pintype "passive"))
      (node (ref "K16") (pin "5") (pinfunction "5_5") (pintype "passive"))
      (node (ref "K32") (pin "5") (pinfunction "5_5") (pintype "passive"))
    )
    (net (code "38") (name "S0") (class "Default")
      (node (ref "K1") (pin "2") (pinfunction "2_2") (pintype "passive"))
      (node (ref "U2") (pin "11") (pinfunction "S0_11") (pintype "passive"))
    )
    (net (code "39") (name "S0_2") (class "Default")
      (node (ref "K17") (pin "2") (pinfunction "2_2") (pintype "passive"))
      (node (ref "U1") (pin "11") (pinfunction "S0_11") (pintype "passive"))
    )
    (net (code "40") (name "S1") (class "Default")
      (node (ref "K2") (pin "2") (pinfunction "2_2") (pintype "passive"))
      (node (ref "U2") (pin "9") (pinfunction "S1_9") (pintype "passive"))
    )
    (net (code "41") (name "S1_2") (class "Default")
      (node (ref "K18") (pin "2") (pinfunction "2_2") (pintype "passive"))
      (node (ref "U1") (pin "9") (pinfunction "S1_9") (pintype "passive"))
    )
    (net (code "42") (name "S2") (class "Default")
      (node (ref "K3") (pin "2") (pinfunction "2_2") (pintype "passive"))
      (node (ref "U2") (pin "10") (pinfunction "S2_10") (pintype "passive"))
    )
    (net (code "43") (name "S2_2") (class "Default")
      (node (ref "K19") (pin "2") (pinfunction "2_2") (pintype "passive"))
      (node (ref "U1") (pin "10") (pinfunction "S2_10") (pintype "passive"))
    )
    (net (code "44") (name "S3") (class "Default")
      (node (ref "K4") (pin "2") (pinfunction "2_2") (pintype "passive"))
      (node (ref "U2") (pin "8") (pinfunction "S3_8") (pintype "passive"))
    )
    (net (code "45") (name "S3_2") (class "Default")
      (node (ref "K20") (pin "2") (pinfunction "2_2") (pintype "passive"))
      (node (ref "U1") (pin "8") (pinfunction "S3_8") (pintype "passive"))
    )
    (net (code "46") (name "S4") (class "Default")
      (node (ref "K5") (pin "2") (pinfunction "2_2") (pintype "passive"))
      (node (ref "U2") (pin "7") (pinfunction "S4_7") (pintype "passive"))
    )
    (net (code "47") (name "S4_2") (class "Default")
      (node (ref "K21") (pin "2") (pinfunction "2_2") (pintype "passive"))
      (node (ref "U1") (pin "7") (pinfunction "S4_7") (pintype "passive"))
    )
    (net (code "48") (name "S5") (class "Default")
      (node (ref "K6") (pin "2") (pinfunction "2_2") (pintype "passive"))
      (node (ref "U2") (pin "6") (pinfunction "S5_6") (pintype "passive"))
    )
    (net (code "49") (name "S5_2") (class "Default")
      (node (ref "K22") (pin "2") (pinfunction "2_2") (pintype "passive"))
      (node (ref "U1") (pin "6") (pinfunction "S5_6") (pintype "passive"))
    )
    (net (code "50") (name "S6") (class "Default")
      (node (ref "K7") (pin "2") (pinfunction "2_2") (pintype "passive"))
      (node (ref "U2") (pin "5") (pinfunction "S6_5") (pintype "passive"))
    )
    (net (code "51") (name "S6_2") (class "Default")
      (node (ref "K23") (pin "2") (pinfunction "2_2") (pintype "passive"))
      (node (ref "U1") (pin "5") (pinfunction "S6_5") (pintype "passive"))
    )
    (net (code "52") (name "S7") (class "Default")
      (node (ref "K8") (pin "2") (pinfunction "2_2") (pintype "passive"))
      (node (ref "U2") (pin "4") (pinfunction "S7_4") (pintype "passive"))
    )
    (net (code "53") (name "S7_2") (class "Default")
      (node (ref "K24") (pin "2") (pinfunction "2_2") (pintype "passive"))
      (node (ref "U1") (pin "4") (pinfunction "S7_4") (pintype "passive"))
    )
    (net (code "54") (name "S8") (class "Default")
      (node (ref "K9") (pin "2") (pinfunction "2_2") (pintype "passive"))
      (node (ref "U2") (pin "18") (pinfunction "S8_18") (pintype "passive"))
    )
    (net (code "55") (name "S8_2") (class "Default")
      (node (ref "K25") (pin "2") (pinfunction "2_2") (pintype "passive"))
      (node (ref "U1") (pin "18") (pinfunction "S8_18") (pintype "passive"))
    )
    (net (code "56") (name "S9") (class "Default")
      (node (ref "K10") (pin "2") (pinfunction "2_2") (pintype "passive"))
      (node (ref "U2") (pin "17") (pinfunction "S9_17") (pintype "passive"))
    )
    (net (code "57") (name "S9_2") (class "Default")
      (node (ref "K26") (pin "2") (pinfunction "2_2") (pintype "passive"))
      (node (ref "U1") (pin "17") (pinfunction "S9_17") (pintype "passive"))
    )
    (net (code "58") (name "S10") (class "Default")
      (node (ref "K11") (pin "2") (pinfunction "2_2") (pintype "passive"))
      (node (ref "U2") (pin "20") (pinfunction "S10_20") (pintype "passive"))
    )
    (net (code "59") (name "S10_2") (class "Default")
      (node (ref "K27") (pin "2") (pinfunction "2_2") (pintype "passive"))
      (node (ref "U1") (pin "20") (pinfunction "S10_20") (pintype "passive"))
    )
    (net (code "60") (name "S11") (class "Default")
      (node (ref "K12") (pin "2") (pinfunction "2_2") (pintype "passive"))
      (node (ref "U2") (pin "19") (pinfunction "S11_19") (pintype "passive"))
    )
    (net (code "61") (name "S11_2") (class "Default")
      (node (ref "K28") (pin "2") (pinfunction "2_2") (pintype "passive"))
      (node (ref "U1") (pin "19") (pinfunction "S11_19") (pintype "passive"))
    )
    (net (code "62") (name "S12") (class "Default")
      (node (ref "K13") (pin "2") (pinfunction "2_2") (pintype "passive"))
      (node (ref "U2") (pin "14") (pinfunction "S12_14") (pintype "passive"))
    )
    (net (code "63") (name "S12_2") (class "Default")
      (node (ref "K29") (pin "2") (pinfunction "2_2") (pintype "passive"))
      (node (ref "U1") (pin "14") (pinfunction "S12_14") (pintype "passive"))
    )
    (net (code "64") (name "S13") (class "Default")
      (node (ref "K14") (pin "2") (pinfunction "2_2") (pintype "passive"))
      (node (ref "U2") (pin "13") (pinfunction "S13_13") (pintype "passive"))
    )
    (net (code "65") (name "S13_2") (class "Default")
      (node (ref "K30") (pin "2") (pinfunction "2_2") (pintype "passive"))
      (node (ref "U1") (pin "13") (pinfunction "S13_13") (pintype "passive"))
    )
    (net (code "66") (name "S14") (class "Default")
      (node (ref "K15") (pin "2") (pinfunction "2_2") (pintype "passive"))
      (node (ref "U2") (pin "16") (pinfunction "S14_16") (pintype "passive"))
    )
    (net (code "67") (name "S14_2") (class "Default")
      (node (ref "K31") (pin "2") (pinfunction "2_2") (pintype "passive"))
      (node (ref "U1") (pin "16") (pinfunction "S14_16") (pintype "passive"))
    )
    (net (code "68") (name "S15") (class "Default")
      (node (ref "K16") (pin "2") (pinfunction "2_2") (pintype "passive"))
      (node (ref "U2") (pin "15") (pinfunction "S15_15") (pintype "passive"))
    )
    (net (code "69") (name "S15_2") (class "Default")
      (node (ref "K32") (pin "2") (pinfunction "2_2") (pintype "passive"))
      (node (ref "U1") (pin "15") (pinfunction "S15_15") (pintype "passive"))
    )
    (net (code "70") (name "SRC1") (class "Default")
      (node (ref "C1") (pin "1") (pinfunction "1_1") (pintype "passive"))
      (node (ref "C2") (pin "1") (pinfunction "1_1") (pintype "passive"))
      (node (ref "C3") (pin "1") (pinfunction "1_1") (pintype "passive"))
      (node (ref "JP5") (pin "1") (pinfunction "1_1") (pintype "passive"))
      (node (ref "K1") (pin "8") (pinfunction "8_8") (pintype "passive"))
      (node (ref "K10") (pin "8") (pinfunction "8_8") (pintype "passive"))
      (node (ref "K11") (pin "8") (pinfunction "8_8") (pintype "passive"))
      (node (ref "K12") (pin "8") (pinfunction "8_8") (pintype "passive"))
      (node (ref "K13") (pin "8") (pinfunction "8_8") (pintype "passive"))
      (node (ref "K14") (pin "8") (pinfunction "8_8") (pintype "passive"))
      (node (ref "K15") (pin "8") (pinfunction "8_8") (pintype "passive"))
      (node (ref "K16") (pin "8") (pinfunction "8_8") (pintype "passive"))
      (node (ref "K2") (pin "8") (pinfunction "8_8") (pintype "passive"))
      (node (ref "K3") (pin "8") (pinfunction "8_8") (pintype "passive"))
      (node (ref "K4") (pin "8") (pinfunction "8_8") (pintype "passive"))
      (node (ref "K5") (pin "8") (pinfunction "8_8") (pintype "passive"))
      (node (ref "K6") (pin "8") (pinfunction "8_8") (pintype "passive"))
      (node (ref "K7") (pin "8") (pinfunction "8_8") (pintype "passive"))
      (node (ref "K8") (pin "8") (pinfunction "8_8") (pintype "passive"))
      (node (ref "K9") (pin "8") (pinfunction "8_8") (pintype "passive"))
      (node (ref "SRC1") (pin "1") (pinfunction "1_1") (pintype "passive"))
    )
    (net (code "71") (name "SRC2") (class "Default")
      (node (ref "C4") (pin "1") (pinfunction "1_1") (pintype "passive"))
      (node (ref "C5") (pin "1") (pinfunction "1_1") (pintype "passive"))
      (node (ref "C6") (pin "1") (pinfunction "1_1") (pintype "passive"))
      (node (ref "JP6") (pin "1") (pinfunction "1_1") (pintype "passive"))
      (node (ref "K17") (pin "8") (pinfunction "8_8") (pintype "passive"))
      (node (ref "K18") (pin "8") (pinfunction "8_8") (pintype "passive"))
      (node (ref "K19") (pin "8") (pinfunction "8_8") (pintype "passive"))
      (node (ref "K20") (pin "8") (pinfunction "8_8") (pintype "passive"))
      (node (ref "K21") (pin "8") (pinfunction "8_8") (pintype "passive"))
      (node (ref "K22") (pin "8") (pinfunction "8_8") (pintype "passive"))
      (node (ref "K23") (pin "8") (pinfunction "8_8") (pintype "passive"))
      (node (ref "K24") (pin "8") (pinfunction "8_8") (pintype "passive"))
      (node (ref "K25") (pin "8") (pinfunction "8_8") (pintype "passive"))
      (node (ref "K26") (pin "8") (pinfunction "8_8") (pintype "passive"))
      (node (ref "K27") (pin "8") (pinfunction "8_8") (pintype "passive"))
      (node (ref "K28") (pin "8") (pinfunction "8_8") (pintype "passive"))
      (node (ref "K29") (pin "8") (pinfunction "8_8") (pintype "passive"))
      (node (ref "K30") (pin "8") (pinfunction "8_8") (pintype "passive"))
      (node (ref "K31") (pin "8") (pinfunction "8_8") (pintype "passive"))
      (node (ref "K32") (pin "8") (pinfunction "8_8") (pintype "passive"))
      (node (ref "SRC2") (pin "1") (pinfunction "1_1") (pintype "passive"))
    )
    (net (code "72") (name "ST") (class "Default")
      (node (ref "U1") (pin "1") (pinfunction "ST_1") (pintype "passive"))
      (node (ref "U2") (pin "1") (pinfunction "ST_1") (pintype "passive"))
      (node (ref "U4") (pin "12") (pinfunction "EOUT_12") (pintype "output"))
    )
    (net (code "73") (name "ST_C") (class "Default")
      (node (ref "JP9") (pin "2") (pinfunction "2_2") (pintype "passive"))
      (node (ref "U4") (pin "11") (pinfunction "EIN_11") (pintype "input"))
    )
    (net (code "74") (name "unconnected-(U3-EIN-Pad11)") (class "Default")
      (node (ref "U3") (pin "11") (pinfunction "EIN_11") (pintype "input"))
    )
    (net (code "75") (name "unconnected-(U3-EOUT-Pad12)") (class "Default")
      (node (ref "U3") (pin "12") (pinfunction "EOUT_12") (pintype "output"))
    )
    (net (code "76") (name "unconnected-(U3-FIN-Pad14)") (class "Default")
      (node (ref "U3") (pin "14") (pinfunction "FIN_14") (pintype "input"))
    )
    (net (code "77") (name "unconnected-(U3-FOUT-Pad15)") (class "Default")
      (node (ref "U3") (pin "15") (pinfunction "FOUT_15") (pintype "output"))
    )
  )
)
